# Dongle.net
KiCad netlist of a schematic drawn in EAGLE
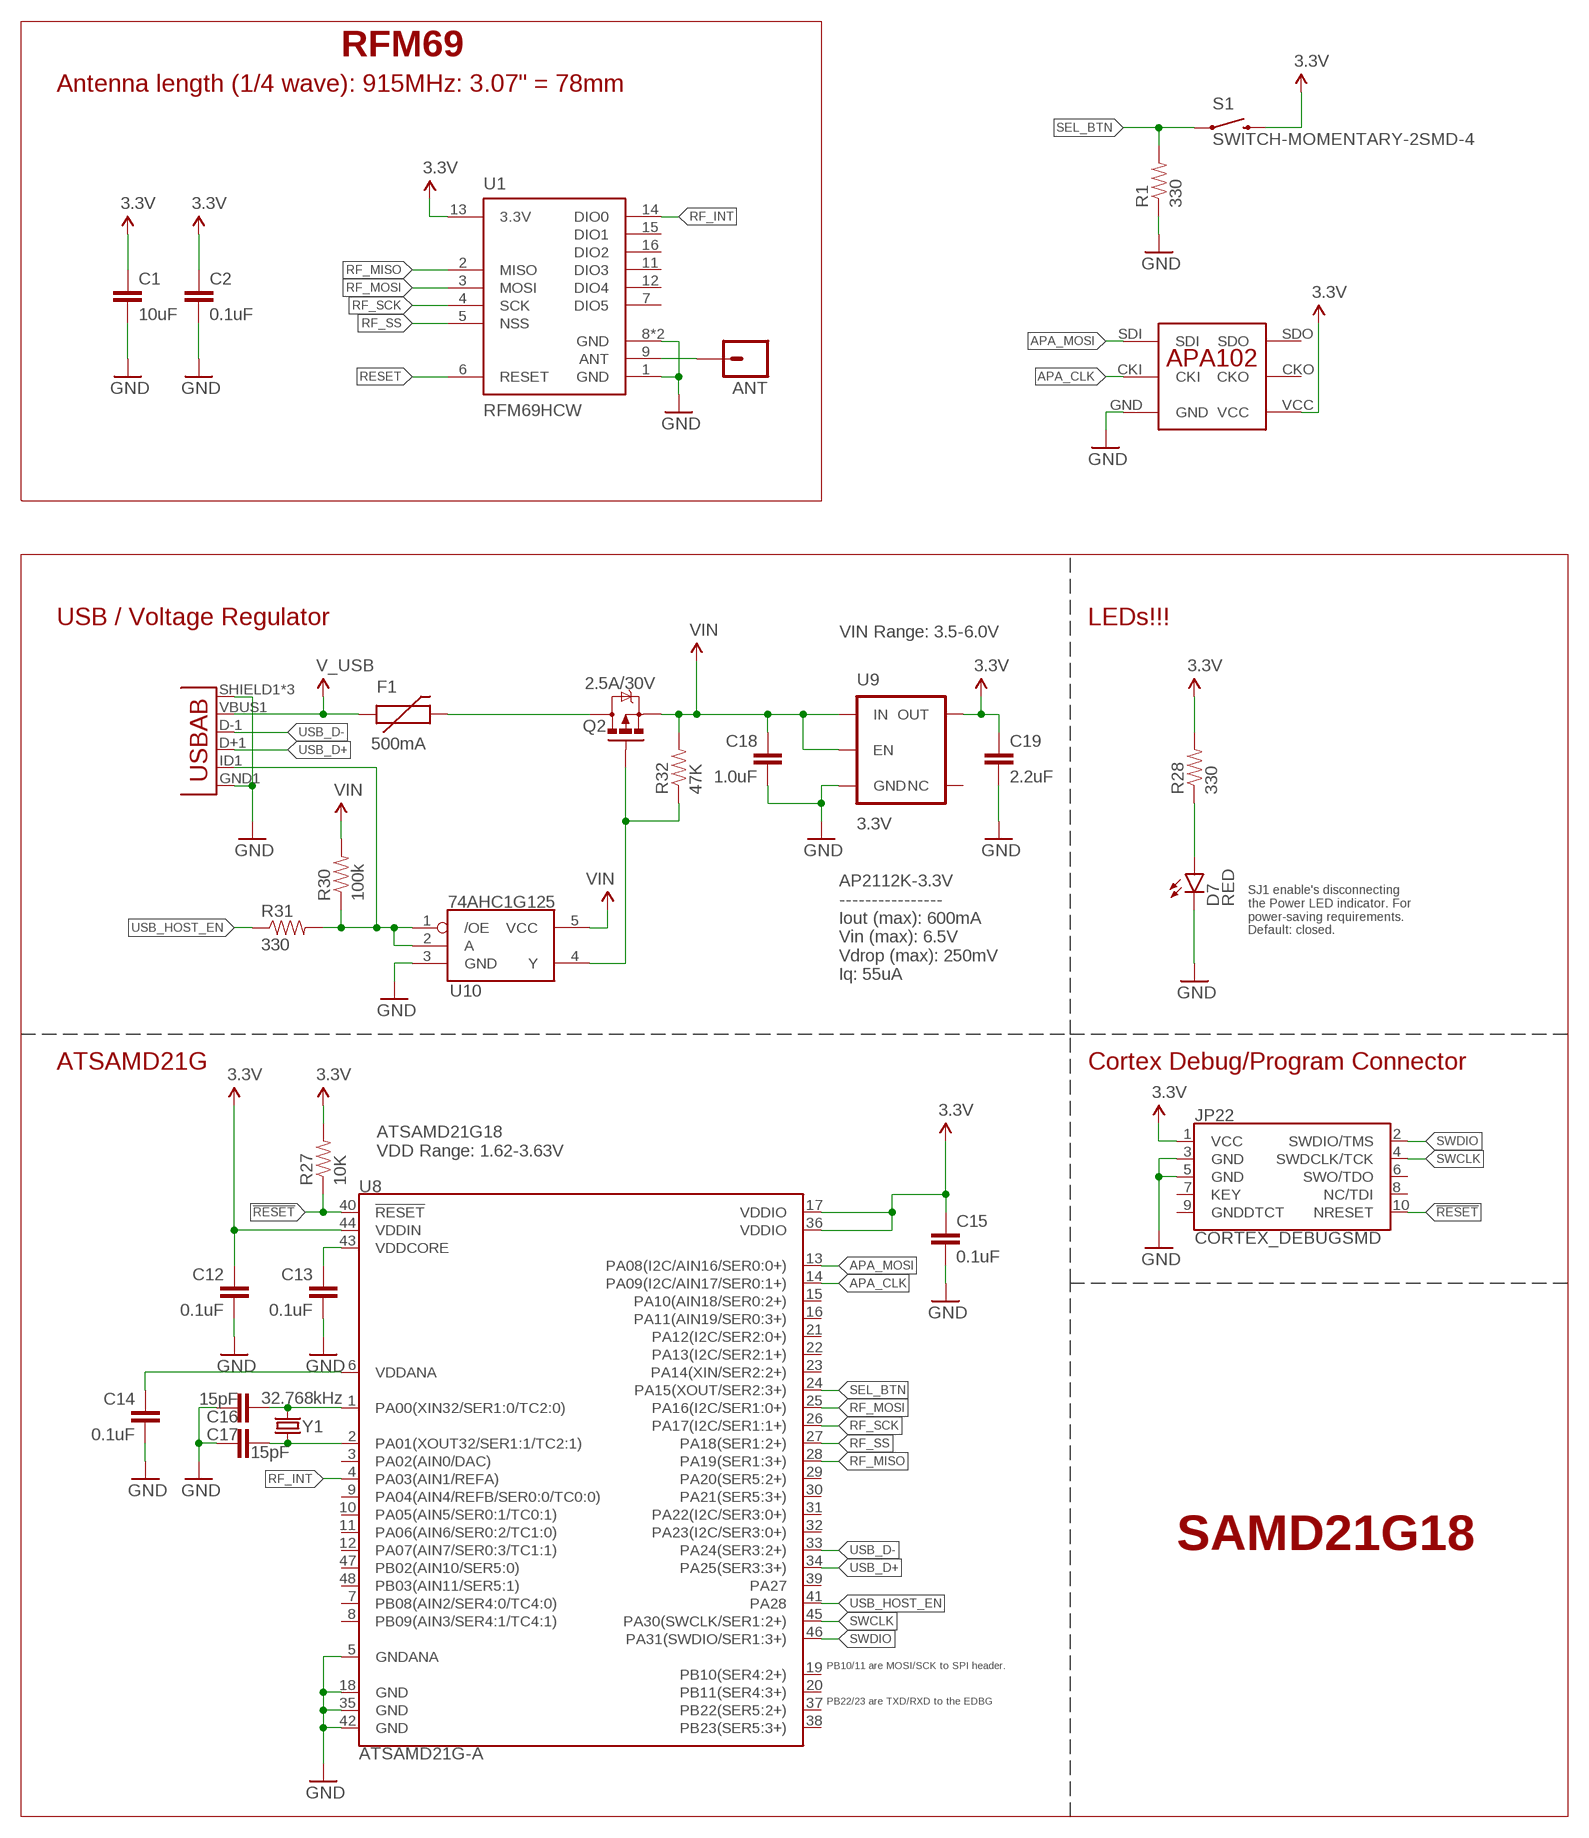
[diagram p0: schematic, sheet 1]

(export (version "E")
  (design (tool "Eeschema 10.0.6"))
  (components
    (comp (ref "ANT")
      (value "M01PTH_NO_SILK_YES_STOP")
      (footprint "eagle-import:1X01_NO_SILK")
      (libsource (lib "eagle-import") (part "M01PTH_NO_SILK_YES_STOP"))
    )
    (comp (ref "C1")
      (value "10uF")
      (footprint "eagle-import:1210")
      (libsource (lib "eagle-import") (part "10UF50V20%(1210)"))
    )
    (comp (ref "C2")
      (value "0.1uF")
      (footprint "eagle-import:0603-CAP@1")
      (libsource (lib "eagle-import") (part "0.1UF-25V(+80/-20%)(0603)"))
    )
    (comp (ref "C12")
      (value "0.1uF")
      (footprint "eagle-import:0402-CAP")
      (libsource (lib "eagle-import") (part "0.1UF-16V(+-10%)(0402)"))
    )
    (comp (ref "C13")
      (value "0.1uF")
      (footprint "eagle-import:0402-CAP")
      (libsource (lib "eagle-import") (part "0.1UF-16V(+-10%)(0402)"))
    )
    (comp (ref "C14")
      (value "0.1uF")
      (footprint "eagle-import:0402-CAP")
      (libsource (lib "eagle-import") (part "0.1UF-16V(+-10%)(0402)"))
    )
    (comp (ref "C15")
      (value "0.1uF")
      (footprint "eagle-import:0402-CAP")
      (libsource (lib "eagle-import") (part "0.1UF-16V(+-10%)(0402)"))
    )
    (comp (ref "C16")
      (value "15pF")
      (footprint "eagle-import:0402-CAP")
      (libsource (lib "eagle-import") (part "15PF-50V(+-5%)(0402)"))
    )
    (comp (ref "C17")
      (value "15pF")
      (footprint "eagle-import:0402-CAP")
      (libsource (lib "eagle-import") (part "15PF-50V(+-5%)(0402)"))
    )
    (comp (ref "C18")
      (value "1.0uF")
      (footprint "eagle-import:0805-CAP")
      (libsource (lib "eagle-import") (part "1.0UF-25V-+80/-20(0805){dblquote}"))
    )
    (comp (ref "C19")
      (value "2.2uF")
      (footprint "eagle-import:0603-CAP")
      (libsource (lib "eagle-import") (part "2.2UF-10V-20%(0603)"))
    )
    (comp (ref "D7")
      (value "RED")
      (footprint "eagle-import:LED-0603")
      (libsource (lib "eagle-import") (part "LED-RED0603"))
    )
    (comp (ref "F1")
      (value "500mA")
      (footprint "eagle-import:PTC-1206")
      (libsource (lib "eagle-import") (part "PTCSMD"))
    )
    (comp (ref "JP22")
      (value "CORTEX_DEBUGSMD")
      (footprint "eagle-import:SAMTECH_FTSH-105-01")
      (libsource (lib "eagle-import") (part "CORTEX_DEBUGSMD"))
    )
    (comp (ref "JP23")
      (value "USB-ABCONN-11794")
      (footprint "eagle-import:USB-AB-MICRO-SMD_V03")
      (libsource (lib "eagle-import") (part "USB-ABCONN-11794"))
    )
    (comp (ref "Q2")
      (value "2.5A/30V")
      (footprint "eagle-import:SOT23-3")
      (libsource (lib "eagle-import") (part "MOSFET-PCHANNELDMG2307L"))
    )
    (comp (ref "R1")
      (value "330")
      (footprint "eagle-import:0603-RES")
      (libsource (lib "eagle-import") (part "330OHM1/10W1%(0603)"))
    )
    (comp (ref "R27")
      (value "10K")
      (footprint "eagle-import:0603-RES")
      (libsource (lib "eagle-import") (part "10KOHM-1/10W-1%(0603)0603"))
    )
    (comp (ref "R28")
      (value "330")
      (footprint "eagle-import:0603-RES")
      (libsource (lib "eagle-import") (part "330OHM1/10W1%(0603)"))
    )
    (comp (ref "R30")
      (value "100k")
      (footprint "eagle-import:0603-RES")
      (libsource (lib "eagle-import") (part "100KOHM-1/10W-1%(0603)"))
    )
    (comp (ref "R31")
      (value "330")
      (footprint "eagle-import:0603-RES")
      (libsource (lib "eagle-import") (part "330OHM1/10W1%(0603)"))
    )
    (comp (ref "R32")
      (value "47K")
      (footprint "eagle-import:0603-RES")
      (libsource (lib "eagle-import") (part "47KOHM1/10W1%(0603)"))
    )
    (comp (ref "S1")
      (value "SWITCH-MOMENTARY-2SMD-4")
      (footprint "eagle-import:TACTILE_SWITCH_TALL")
      (libsource (lib "eagle-import") (part "SWITCH-MOMENTARY-2SMD-4"))
    )
    (comp (ref "U$1")
      (value "APA102")
      (footprint "eagle-import:APA102")
      (libsource (lib "eagle-import") (part "APA102"))
    )
    (comp (ref "U1")
      (value "RFM69HCW")
      (footprint "eagle-import:RFM69HCW-XXXS2")
      (libsource (lib "eagle-import") (part "RFM69HCW"))
    )
    (comp (ref "U8")
      (value "ATSAMD21G-A")
      (footprint "eagle-import:TQFP-48")
      (libsource (lib "eagle-import") (part "ATSAMD21G-A"))
    )
    (comp (ref "U9")
      (value "3.3V")
      (footprint "eagle-import:SOT23-5")
      (libsource (lib "eagle-import") (part "V_REG_AP2112K-3.3V"))
    )
    (comp (ref "U10")
      (value "74AHC1G125")
      (footprint "eagle-import:SOT23-5")
      (libsource (lib "eagle-import") (part "74AHC1G125"))
    )
    (comp (ref "Y1")
      (value "32.768kHz")
      (footprint "eagle-import:CRYSTAL-SMD-3.2X1.5MM")
      (libsource (lib "eagle-import") (part "CRYSTAL3.2X1.5MM"))
    )
  )
  (nets
    (net (code "1") (name "/~{RESET}") (class "Default")
      (node (ref "JP22") (pin "10") (pinfunction "NRESET_10") (pintype "bidirectional"))
      (node (ref "R27") (pin "1") (pinfunction "1_1") (pintype "passive"))
      (node (ref "U8") (pin "40") (pinfunction "~{RESET}_40") (pintype "bidirectional"))
    )
    (net (code "2") (name "3.3V") (class "Default")
      (node (ref "C1") (pin "1") (pinfunction "1_1") (pintype "passive"))
      (node (ref "C12") (pin "1") (pinfunction "1_1") (pintype "passive"))
      (node (ref "C15") (pin "1") (pinfunction "1_1") (pintype "passive"))
      (node (ref "C19") (pin "1") (pinfunction "1_1") (pintype "passive"))
      (node (ref "C2") (pin "1") (pinfunction "1_1") (pintype "passive"))
      (node (ref "JP22") (pin "1") (pinfunction "VCC_1") (pintype "bidirectional"))
      (node (ref "R27") (pin "2") (pinfunction "2_2") (pintype "passive"))
      (node (ref "R28") (pin "2") (pinfunction "2_2") (pintype "passive"))
      (node (ref "S1") (pin "B2") (pinfunction "2_B2") (pintype "passive"))
      (node (ref "U$1") (pin "VCC") (pinfunction "VCC_VCC") (pintype "bidirectional"))
      (node (ref "U1") (pin "13") (pinfunction "3.3V_13") (pintype "power_in"))
      (node (ref "U8") (pin "17") (pinfunction "VDDIO_17") (pintype "bidirectional"))
      (node (ref "U8") (pin "36") (pinfunction "VDDIO_36") (pintype "bidirectional"))
      (node (ref "U8") (pin "44") (pinfunction "VDDIN_44") (pintype "bidirectional"))
      (node (ref "U9") (pin "5") (pinfunction "OUT_5") (pintype "passive"))
    )
    (net (code "3") (name "APA_CLK") (class "Default")
      (node (ref "U$1") (pin "CKI") (pinfunction "CKI_CKI") (pintype "bidirectional"))
      (node (ref "U8") (pin "14") (pinfunction "PA09(I2C/AIN17/SER0:1+)_14") (pintype "bidirectional"))
    )
    (net (code "4") (name "APA_MOSI") (class "Default")
      (node (ref "U$1") (pin "SDI") (pinfunction "SDI_SDI") (pintype "bidirectional"))
      (node (ref "U8") (pin "13") (pinfunction "PA08(I2C/AIN16/SER0:0+)_13") (pintype "bidirectional"))
    )
    (net (code "5") (name "GND") (class "Default")
      (node (ref "C1") (pin "2") (pinfunction "2_2") (pintype "passive"))
      (node (ref "C12") (pin "2") (pinfunction "2_2") (pintype "passive"))
      (node (ref "C13") (pin "2") (pinfunction "2_2") (pintype "passive"))
      (node (ref "C14") (pin "2") (pinfunction "2_2") (pintype "passive"))
      (node (ref "C15") (pin "2") (pinfunction "2_2") (pintype "passive"))
      (node (ref "C16") (pin "1") (pinfunction "1_1") (pintype "passive"))
      (node (ref "C17") (pin "2") (pinfunction "2_2") (pintype "passive"))
      (node (ref "C18") (pin "2") (pinfunction "2_2") (pintype "passive"))
      (node (ref "C19") (pin "2") (pinfunction "2_2") (pintype "passive"))
      (node (ref "C2") (pin "2") (pinfunction "2_2") (pintype "passive"))
      (node (ref "D7") (pin "C") (pinfunction "C_C") (pintype "passive"))
      (node (ref "JP22") (pin "3") (pinfunction "GND_3") (pintype "bidirectional"))
      (node (ref "JP22") (pin "5") (pinfunction "GND_5") (pintype "bidirectional"))
      (node (ref "JP23") (pin "GND1") (pinfunction "GND_GND1") (pintype "bidirectional"))
      (node (ref "JP23") (pin "SHIELD1") (pinfunction "SHIELD_SHIELD1") (pintype "bidirectional"))
      (node (ref "JP23") (pin "SHIELD2") (pinfunction "SHIELD_SHIELD2") (pintype "bidirectional"))
      (node (ref "JP23") (pin "SHIELD3") (pinfunction "SHIELD_SHIELD3") (pintype "bidirectional"))
      (node (ref "R1") (pin "1") (pinfunction "1_1") (pintype "passive"))
      (node (ref "U$1") (pin "GND") (pinfunction "GND_GND") (pintype "bidirectional"))
      (node (ref "U1") (pin "1") (pinfunction "GND_1") (pintype "power_in"))
      (node (ref "U1") (pin "10") (pinfunction "GND_10") (pintype "power_in"))
      (node (ref "U1") (pin "8") (pinfunction "GND_8") (pintype "power_in"))
      (node (ref "U10") (pin "3") (pinfunction "GND_3") (pintype "bidirectional"))
      (node (ref "U8") (pin "18") (pinfunction "GND_18") (pintype "bidirectional"))
      (node (ref "U8") (pin "35") (pinfunction "GND_35") (pintype "bidirectional"))
      (node (ref "U8") (pin "42") (pinfunction "GND_42") (pintype "bidirectional"))
      (node (ref "U8") (pin "5") (pinfunction "GNDANA_5") (pintype "bidirectional"))
      (node (ref "U9") (pin "2") (pinfunction "GND_2") (pintype "input"))
    )
    (net (code "6") (name "Net-(D7-PadA)") (class "Default")
      (node (ref "D7") (pin "A") (pinfunction "A_A") (pintype "passive"))
      (node (ref "R28") (pin "1") (pinfunction "1_1") (pintype "passive"))
    )
    (net (code "7") (name "Net-(JP23-USBID)") (class "Default")
      (node (ref "JP23") (pin "ID1") (pinfunction "USBID_ID1") (pintype "bidirectional"))
      (node (ref "R30") (pin "1") (pinfunction "1_1") (pintype "passive"))
      (node (ref "R31") (pin "2") (pinfunction "2_2") (pintype "passive"))
      (node (ref "U10") (pin "1") (pinfunction "/OE_1") (pintype "bidirectional"))
      (node (ref "U10") (pin "2") (pinfunction "A_2") (pintype "bidirectional"))
    )
    (net (code "8") (name "Net-(Q2-D)") (class "Default")
      (node (ref "F1") (pin "2") (pinfunction "2_2") (pintype "bidirectional"))
      (node (ref "Q2") (pin "3") (pinfunction "D_3") (pintype "passive"))
    )
    (net (code "9") (name "Net-(Q2-G)") (class "Default")
      (node (ref "Q2") (pin "1") (pinfunction "G_1") (pintype "passive"))
      (node (ref "R32") (pin "1") (pinfunction "1_1") (pintype "passive"))
      (node (ref "U10") (pin "4") (pinfunction "Y_4") (pintype "bidirectional"))
    )
    (net (code "10") (name "Net-(U1-ANT)") (class "Default")
      (node (ref "ANT") (pin "1") (pinfunction "1_1") (pintype "passive"))
      (node (ref "U1") (pin "9") (pinfunction "ANT_9") (pintype "passive"))
    )
    (net (code "11") (name "Net-(U8-PA00(XIN32{slash}SER1:0{slash}TC2:0))") (class "Default")
      (node (ref "C16") (pin "2") (pinfunction "2_2") (pintype "passive"))
      (node (ref "U8") (pin "1") (pinfunction "PA00(XIN32/SER1:0/TC2:0)_1") (pintype "bidirectional"))
      (node (ref "Y1") (pin "P$2") (pinfunction "2_P$2") (pintype "passive"))
    )
    (net (code "12") (name "Net-(U8-PA01(XOUT32{slash}SER1:1{slash}TC2:1))") (class "Default")
      (node (ref "C17") (pin "1") (pinfunction "1_1") (pintype "passive"))
      (node (ref "U8") (pin "2") (pinfunction "PA01(XOUT32/SER1:1/TC2:1)_2") (pintype "bidirectional"))
      (node (ref "Y1") (pin "P$1") (pinfunction "1_P$1") (pintype "passive"))
    )
    (net (code "13") (name "Net-(U8-VDDANA)") (class "Default")
      (node (ref "C14") (pin "1") (pinfunction "1_1") (pintype "passive"))
      (node (ref "U8") (pin "6") (pinfunction "VDDANA_6") (pintype "bidirectional"))
    )
    (net (code "14") (name "Net-(U8-VDDCORE)") (class "Default")
      (node (ref "C13") (pin "1") (pinfunction "1_1") (pintype "passive"))
      (node (ref "U8") (pin "43") (pinfunction "VDDCORE_43") (pintype "bidirectional"))
    )
    (net (code "15") (name "RESET") (class "Default")
      (node (ref "U1") (pin "6") (pinfunction "RESET_6") (pintype "input"))
    )
    (net (code "16") (name "RF_INT") (class "Default")
      (node (ref "U1") (pin "14") (pinfunction "DIO0_14") (pintype "bidirectional"))
      (node (ref "U8") (pin "4") (pinfunction "PA03(AIN1/REFA)_4") (pintype "bidirectional"))
    )
    (net (code "17") (name "RF_MISO") (class "Default")
      (node (ref "U1") (pin "2") (pinfunction "MISO_2") (pintype "bidirectional"))
      (node (ref "U8") (pin "28") (pinfunction "PA19(SER1:3+)_28") (pintype "bidirectional"))
    )
    (net (code "18") (name "RF_MOSI") (class "Default")
      (node (ref "U1") (pin "3") (pinfunction "MOSI_3") (pintype "input"))
      (node (ref "U8") (pin "25") (pinfunction "PA16(I2C/SER1:0+)_25") (pintype "bidirectional"))
    )
    (net (code "19") (name "RF_SCK") (class "Default")
      (node (ref "U1") (pin "4") (pinfunction "SCK_4") (pintype "input"))
      (node (ref "U8") (pin "26") (pinfunction "PA17(I2C/SER1:1+)_26") (pintype "bidirectional"))
    )
    (net (code "20") (name "RF_SS") (class "Default")
      (node (ref "U1") (pin "5") (pinfunction "NSS_5") (pintype "input"))
      (node (ref "U8") (pin "27") (pinfunction "PA18(SER1:2+)_27") (pintype "bidirectional"))
    )
    (net (code "21") (name "SEL_BTN") (class "Default")
      (node (ref "R1") (pin "2") (pinfunction "2_2") (pintype "passive"))
      (node (ref "S1") (pin "A2") (pinfunction "1_A2") (pintype "passive"))
      (node (ref "U8") (pin "24") (pinfunction "PA15(XOUT/SER2:3+)_24") (pintype "bidirectional"))
    )
    (net (code "22") (name "SWCLK") (class "Default")
      (node (ref "JP22") (pin "4") (pinfunction "SWDCLK/TCK_4") (pintype "bidirectional"))
      (node (ref "U8") (pin "45") (pinfunction "PA30(SWCLK/SER1:2+)_45") (pintype "bidirectional"))
    )
    (net (code "23") (name "SWDIO") (class "Default")
      (node (ref "JP22") (pin "2") (pinfunction "SWDIO/TMS_2") (pintype "bidirectional"))
      (node (ref "U8") (pin "46") (pinfunction "PA31(SWDIO/SER1:3+)_46") (pintype "bidirectional"))
    )
    (net (code "24") (name "USB_D+") (class "Default")
      (node (ref "JP23") (pin "D+1") (pinfunction "D+_D+1") (pintype "bidirectional"))
      (node (ref "U8") (pin "34") (pinfunction "PA25(SER3:3+)_34") (pintype "bidirectional"))
    )
    (net (code "25") (name "USB_D-") (class "Default")
      (node (ref "JP23") (pin "D-1") (pinfunction "D-_D-1") (pintype "bidirectional"))
      (node (ref "U8") (pin "33") (pinfunction "PA24(SER3:2+)_33") (pintype "bidirectional"))
    )
    (net (code "26") (name "USB_HOST_EN") (class "Default")
      (node (ref "R31") (pin "1") (pinfunction "1_1") (pintype "passive"))
      (node (ref "U8") (pin "41") (pinfunction "PA28_41") (pintype "bidirectional"))
    )
    (net (code "27") (name "VIN") (class "Default")
      (node (ref "C18") (pin "1") (pinfunction "1_1") (pintype "passive"))
      (node (ref "Q2") (pin "2") (pinfunction "S_2") (pintype "passive"))
      (node (ref "R30") (pin "2") (pinfunction "2_2") (pintype "passive"))
      (node (ref "R32") (pin "2") (pinfunction "2_2") (pintype "passive"))
      (node (ref "U10") (pin "5") (pinfunction "VCC_5") (pintype "bidirectional"))
      (node (ref "U9") (pin "1") (pinfunction "IN_1") (pintype "input"))
      (node (ref "U9") (pin "3") (pinfunction "EN_3") (pintype "input"))
    )
    (net (code "28") (name "V_USB") (class "Default")
      (node (ref "F1") (pin "1") (pinfunction "1_1") (pintype "bidirectional"))
      (node (ref "JP23") (pin "VBUS1") (pinfunction "VBUS_VBUS1") (pintype "bidirectional"))
    )
    (net (code "29") (name "unconnected-(JP22-GNDDTCT-Pad9)") (class "Default")
      (node (ref "JP22") (pin "9") (pinfunction "GNDDTCT_9") (pintype "bidirectional"))
    )
    (net (code "30") (name "unconnected-(JP22-KEY-Pad7)") (class "Default")
      (node (ref "JP22") (pin "7") (pinfunction "KEY_7") (pintype "bidirectional"))
    )
    (net (code "31") (name "unconnected-(JP22-NC{slash}TDI-Pad8)") (class "Default")
      (node (ref "JP22") (pin "8") (pinfunction "NC/TDI_8") (pintype "bidirectional"))
    )
    (net (code "32") (name "unconnected-(JP22-SWO{slash}TDO-Pad6)") (class "Default")
      (node (ref "JP22") (pin "6") (pinfunction "SWO/TDO_6") (pintype "bidirectional"))
    )
    (net (code "33") (name "unconnected-(U$1-PadCKO)") (class "Default")
      (node (ref "U$1") (pin "CKO") (pinfunction "CKO_CKO") (pintype "bidirectional"))
    )
    (net (code "34") (name "unconnected-(U$1-PadSDO)") (class "Default")
      (node (ref "U$1") (pin "SDO") (pinfunction "SDO_SDO") (pintype "bidirectional"))
    )
    (net (code "35") (name "unconnected-(U1-DIO1-Pad15)") (class "Default")
      (node (ref "U1") (pin "15") (pinfunction "DIO1_15") (pintype "bidirectional"))
    )
    (net (code "36") (name "unconnected-(U1-DIO2-Pad16)") (class "Default")
      (node (ref "U1") (pin "16") (pinfunction "DIO2_16") (pintype "bidirectional"))
    )
    (net (code "37") (name "unconnected-(U1-DIO3-Pad11)") (class "Default")
      (node (ref "U1") (pin "11") (pinfunction "DIO3_11") (pintype "bidirectional"))
    )
    (net (code "38") (name "unconnected-(U1-DIO4-Pad12)") (class "Default")
      (node (ref "U1") (pin "12") (pinfunction "DIO4_12") (pintype "bidirectional"))
    )
    (net (code "39") (name "unconnected-(U1-DIO5-Pad7)") (class "Default")
      (node (ref "U1") (pin "7") (pinfunction "DIO5_7") (pintype "bidirectional"))
    )
    (net (code "40") (name "unconnected-(U8-PA02(AIN0{slash}DAC)-Pad3)") (class "Default")
      (node (ref "U8") (pin "3") (pinfunction "PA02(AIN0/DAC)_3") (pintype "bidirectional"))
    )
    (net (code "41") (name "unconnected-(U8-PA04(AIN4{slash}REFB{slash}SER0:0{slash}TC0:0)-Pad9)") (class "Default")
      (node (ref "U8") (pin "9") (pinfunction "PA04(AIN4/REFB/SER0:0/TC0:0)_9") (pintype "bidirectional"))
    )
    (net (code "42") (name "unconnected-(U8-PA05(AIN5{slash}SER0:1{slash}TC0:1)-Pad10)") (class "Default")
      (node (ref "U8") (pin "10") (pinfunction "PA05(AIN5/SER0:1/TC0:1)_10") (pintype "bidirectional"))
    )
    (net (code "43") (name "unconnected-(U8-PA06(AIN6{slash}SER0:2{slash}TC1:0)-Pad11)") (class "Default")
      (node (ref "U8") (pin "11") (pinfunction "PA06(AIN6/SER0:2/TC1:0)_11") (pintype "bidirectional"))
    )
    (net (code "44") (name "unconnected-(U8-PA07(AIN7{slash}SER0:3{slash}TC1:1)-Pad12)") (class "Default")
      (node (ref "U8") (pin "12") (pinfunction "PA07(AIN7/SER0:3/TC1:1)_12") (pintype "bidirectional"))
    )
    (net (code "45") (name "unconnected-(U8-PA10(AIN18{slash}SER0:2+)-Pad15)") (class "Default")
      (node (ref "U8") (pin "15") (pinfunction "PA10(AIN18/SER0:2+)_15") (pintype "bidirectional"))
    )
    (net (code "46") (name "unconnected-(U8-PA11(AIN19{slash}SER0:3+)-Pad16)") (class "Default")
      (node (ref "U8") (pin "16") (pinfunction "PA11(AIN19/SER0:3+)_16") (pintype "bidirectional"))
    )
    (net (code "47") (name "unconnected-(U8-PA12(I2C{slash}SER2:0+)-Pad21)") (class "Default")
      (node (ref "U8") (pin "21") (pinfunction "PA12(I2C/SER2:0+)_21") (pintype "bidirectional"))
    )
    (net (code "48") (name "unconnected-(U8-PA13(I2C{slash}SER2:1+)-Pad22)") (class "Default")
      (node (ref "U8") (pin "22") (pinfunction "PA13(I2C/SER2:1+)_22") (pintype "bidirectional"))
    )
    (net (code "49") (name "unconnected-(U8-PA14(XIN{slash}SER2:2+)-Pad23)") (class "Default")
      (node (ref "U8") (pin "23") (pinfunction "PA14(XIN/SER2:2+)_23") (pintype "bidirectional"))
    )
    (net (code "50") (name "unconnected-(U8-PA20(SER5:2+)-Pad29)") (class "Default")
      (node (ref "U8") (pin "29") (pinfunction "PA20(SER5:2+)_29") (pintype "bidirectional"))
    )
    (net (code "51") (name "unconnected-(U8-PA21(SER5:3+)-Pad30)") (class "Default")
      (node (ref "U8") (pin "30") (pinfunction "PA21(SER5:3+)_30") (pintype "bidirectional"))
    )
    (net (code "52") (name "unconnected-(U8-PA22(I2C{slash}SER3:0+)-Pad31)") (class "Default")
      (node (ref "U8") (pin "31") (pinfunction "PA22(I2C/SER3:0+)_31") (pintype "bidirectional"))
    )
    (net (code "53") (name "unconnected-(U8-PA23(I2C{slash}SER3:0+)-Pad32)") (class "Default")
      (node (ref "U8") (pin "32") (pinfunction "PA23(I2C/SER3:0+)_32") (pintype "bidirectional"))
    )
    (net (code "54") (name "unconnected-(U8-PA27-Pad39)") (class "Default")
      (node (ref "U8") (pin "39") (pinfunction "PA27_39") (pintype "bidirectional"))
    )
    (net (code "55") (name "unconnected-(U8-PB02(AIN10{slash}SER5:0)-Pad47)") (class "Default")
      (node (ref "U8") (pin "47") (pinfunction "PB02(AIN10/SER5:0)_47") (pintype "bidirectional"))
    )
    (net (code "56") (name "unconnected-(U8-PB03(AIN11{slash}SER5:1)-Pad48)") (class "Default")
      (node (ref "U8") (pin "48") (pinfunction "PB03(AIN11/SER5:1)_48") (pintype "bidirectional"))
    )
    (net (code "57") (name "unconnected-(U8-PB08(AIN2{slash}SER4:0{slash}TC4:0)-Pad7)") (class "Default")
      (node (ref "U8") (pin "7") (pinfunction "PB08(AIN2/SER4:0/TC4:0)_7") (pintype "bidirectional"))
    )
    (net (code "58") (name "unconnected-(U8-PB09(AIN3{slash}SER4:1{slash}TC4:1)-Pad8)") (class "Default")
      (node (ref "U8") (pin "8") (pinfunction "PB09(AIN3/SER4:1/TC4:1)_8") (pintype "bidirectional"))
    )
    (net (code "59") (name "unconnected-(U8-PB10(SER4:2+)-Pad19)") (class "Default")
      (node (ref "U8") (pin "19") (pinfunction "PB10(SER4:2+)_19") (pintype "bidirectional"))
    )
    (net (code "60") (name "unconnected-(U8-PB11(SER4:3+)-Pad20)") (class "Default")
      (node (ref "U8") (pin "20") (pinfunction "PB11(SER4:3+)_20") (pintype "bidirectional"))
    )
    (net (code "61") (name "unconnected-(U8-PB22(SER5:2+)-Pad37)") (class "Default")
      (node (ref "U8") (pin "37") (pinfunction "PB22(SER5:2+)_37") (pintype "bidirectional"))
    )
    (net (code "62") (name "unconnected-(U8-PB23(SER5:3+)-Pad38)") (class "Default")
      (node (ref "U8") (pin "38") (pinfunction "PB23(SER5:3+)_38") (pintype "bidirectional"))
    )
    (net (code "63") (name "unconnected-(U9-NC-Pad4)") (class "Default")
      (node (ref "U9") (pin "4") (pinfunction "NC_4") (pintype "input"))
    )
  )
)
